# Daughterboard_Headers.net
KiCad netlist of a schematic drawn in Altium Designer
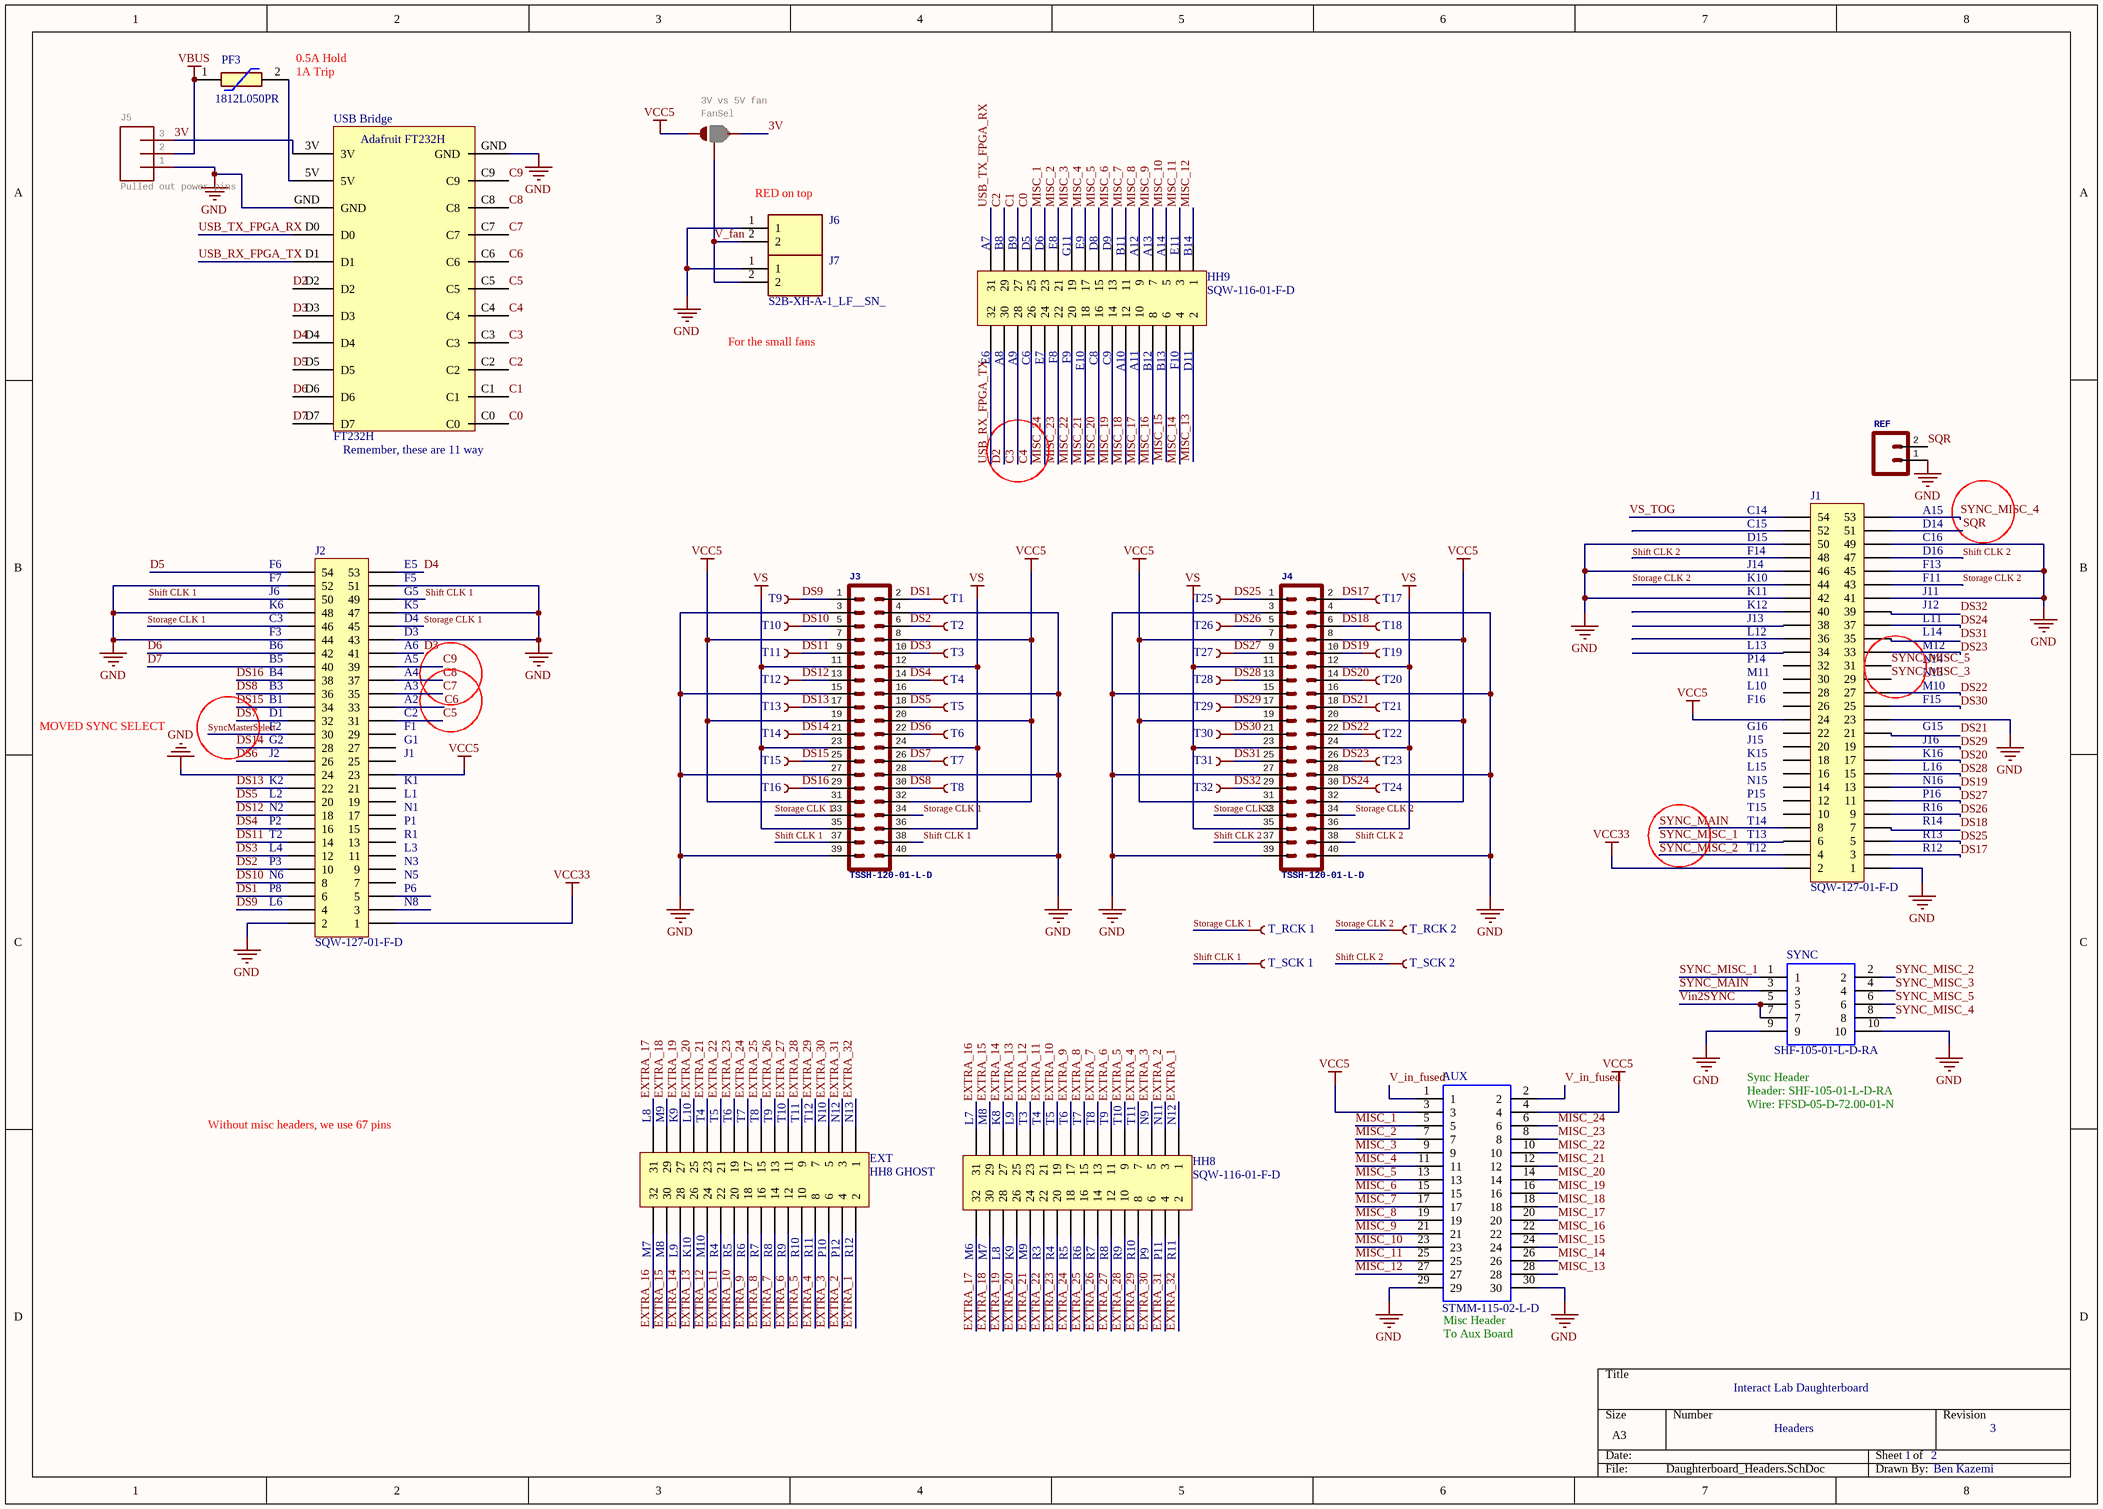
[diagram p0: Daughterboard_Headers.SchDoc]

(export (version "E")
  (design (tool "Eeschema 10.0.6"))
  (components
    (comp (ref "AUX")
      (value "STMM-115-02-L-D")
      (footprint "STMM-115-02-L-D")
      (fields (field (name "RS PART NUMBER") "9012513") (field (name "MOUSER PART NUMBER") "200-STMM11502LD"))
      (libsource (lib "InteractLab") (part "STMM-115-02-L-D"))
    )
    (comp (ref "EXT")
      (value "HH8 GHOST")
      (footprint "HDR2X16")
      (description "Header, 16-Pin, Dual row")
      (fields (field (name "PUBLISHER") "Altium Limited"))
      (libsource (lib "Miscellaneous Connectors") (part "Header 16X2"))
    )
    (comp (ref "FanSel")
      (value "3V vs 5V fan")
      (footprint "SMT-JUMPER_3_1-NC_PASTE_SILK")
      (libsource (lib "SparkFun-Jumpers.Library") (part "JUMPER-SMT_3_1-NC_PASTE_SILK"))
    )
    (comp (ref "HH8")
      (value "SQW-116-01-F-D")
      (footprint "Header 16X2 - 2mm")
      (description "Header, 16-Pin, Dual row")
      (fields (field (name "PUBLISHER") "Altium Limited"))
      (libsource (lib "InteractLab") (part "Header 16X2"))
    )
    (comp (ref "HH9")
      (value "SQW-116-01-F-D")
      (footprint "Header 16X2 - 2mm")
      (description "Header, 16-Pin, Dual row")
      (fields (field (name "PUBLISHER") "Altium Limited"))
      (libsource (lib "InteractLab") (part "Header 16X2"))
    )
    (comp (ref "J1")
      (value "SQW-127-01-F-D")
      (footprint "Header 27X2 - 2mm")
      (description "Header, 30-Pin, Dual row")
      (libsource (lib "InteractLab") (part "Header 27x2"))
    )
    (comp (ref "J2")
      (value "SQW-127-01-F-D")
      (footprint "Header 27X2 - 2mm")
      (description "Header, 30-Pin, Dual row")
      (libsource (lib "InteractLab") (part "Header 27x2"))
    )
    (comp (ref "J3")
      (value "TSSH-120-01-L-D")
      (footprint "2X20_Socket")
      (libsource (lib "InteractLab") (part "CONN_20X2"))
    )
    (comp (ref "J4")
      (value "TSSH-120-01-L-D")
      (footprint "2X20_Socket")
      (libsource (lib "InteractLab") (part "CONN_20X2"))
    )
    (comp (ref "J5")
      (value "Pulled out power pins")
      (footprint "1X03")
      (libsource (lib "SparkFun-Connectors.Library") (part "CONN_03"))
    )
    (comp (ref "J6")
      (value "S2B-XH-A-1_LF__SN_")
      (footprint "SamacSys:S2BXHA1LFSN")
      (description "Connector")
      (fields (field (name "MANUFACTURER_PART_NUMBER") "S2B-XH-A-1(LF)(SN)"))
      (libsource (lib "*") (part "S2B-XH-A-1_LF__SN_"))
    )
    (comp (ref "J7")
      (value "S2B-XH-A-1_LF__SN_")
      (footprint "SamacSys:S2BXHA1LFSN")
      (description "Connector")
      (fields (field (name "MANUFACTURER_PART_NUMBER") "S2B-XH-A-1(LF)(SN)"))
      (libsource (lib "*") (part "S2B-XH-A-1_LF__SN_"))
    )
    (comp (ref "PF3")
      (value "1812L050PR")
      (footprint "SamacSys:1812L010DR")
      (description "Resettable Fuse")
      (fields (field (name "MOUSER PART NUMBER") "576-1812L050PR"))
      (libsource (lib "*") (part "1812L050PR"))
    )
    (comp (ref "REF")
      (value "~")
      (footprint "1X02_LOCK_")
      (libsource (lib "SparkFun-Connectors") (part "CONN_02LOCK"))
    )
    (comp (ref "SYNC")
      (value "SHF-105-01-L-D-RA")
      (footprint "SHF-105-01-L-D-RA")
      (fields (field (name "RS PART NUMBER") "9011850"))
      (libsource (lib "InteractLab") (part "1.27mm Header 2x05 SHF-105-01-L-D-RA"))
    )
    (comp (ref "T1")
      (value "TEST-POINT3X5")
      (footprint "PAD.03X.05")
      (libsource (lib "SparkFun-Connectors") (part "TEST-POINT3X5"))
    )
    (comp (ref "T2")
      (value "TEST-POINT3X5")
      (footprint "PAD.03X.05")
      (libsource (lib "SparkFun-Connectors") (part "TEST-POINT3X5"))
    )
    (comp (ref "T3")
      (value "TEST-POINT3X5")
      (footprint "PAD.03X.05")
      (libsource (lib "SparkFun-Connectors") (part "TEST-POINT3X5"))
    )
    (comp (ref "T4")
      (value "TEST-POINT3X5")
      (footprint "PAD.03X.05")
      (libsource (lib "SparkFun-Connectors") (part "TEST-POINT3X5"))
    )
    (comp (ref "T5")
      (value "TEST-POINT3X5")
      (footprint "PAD.03X.05")
      (libsource (lib "SparkFun-Connectors") (part "TEST-POINT3X5"))
    )
    (comp (ref "T6")
      (value "TEST-POINT3X5")
      (footprint "PAD.03X.05")
      (libsource (lib "SparkFun-Connectors") (part "TEST-POINT3X5"))
    )
    (comp (ref "T7")
      (value "TEST-POINT3X5")
      (footprint "PAD.03X.05")
      (libsource (lib "SparkFun-Connectors") (part "TEST-POINT3X5"))
    )
    (comp (ref "T8")
      (value "TEST-POINT3X5")
      (footprint "PAD.03X.05")
      (libsource (lib "SparkFun-Connectors") (part "TEST-POINT3X5"))
    )
    (comp (ref "T9")
      (value "TEST-POINT3X5")
      (footprint "PAD.03X.05")
      (libsource (lib "SparkFun-Connectors") (part "TEST-POINT3X5"))
    )
    (comp (ref "T10")
      (value "TEST-POINT3X5")
      (footprint "PAD.03X.05")
      (libsource (lib "SparkFun-Connectors") (part "TEST-POINT3X5"))
    )
    (comp (ref "T11")
      (value "TEST-POINT3X5")
      (footprint "PAD.03X.05")
      (libsource (lib "SparkFun-Connectors") (part "TEST-POINT3X5"))
    )
    (comp (ref "T12")
      (value "TEST-POINT3X5")
      (footprint "PAD.03X.05")
      (libsource (lib "SparkFun-Connectors") (part "TEST-POINT3X5"))
    )
    (comp (ref "T13")
      (value "TEST-POINT3X5")
      (footprint "PAD.03X.05")
      (libsource (lib "SparkFun-Connectors") (part "TEST-POINT3X5"))
    )
    (comp (ref "T14")
      (value "TEST-POINT3X5")
      (footprint "PAD.03X.05")
      (libsource (lib "SparkFun-Connectors") (part "TEST-POINT3X5"))
    )
    (comp (ref "T15")
      (value "TEST-POINT3X5")
      (footprint "PAD.03X.05")
      (libsource (lib "SparkFun-Connectors") (part "TEST-POINT3X5"))
    )
    (comp (ref "T16")
      (value "TEST-POINT3X5")
      (footprint "PAD.03X.05")
      (libsource (lib "SparkFun-Connectors") (part "TEST-POINT3X5"))
    )
    (comp (ref "T17")
      (value "TEST-POINT3X5")
      (footprint "PAD.03X.05")
      (libsource (lib "SparkFun-Connectors") (part "TEST-POINT3X5"))
    )
    (comp (ref "T18")
      (value "TEST-POINT3X5")
      (footprint "PAD.03X.05")
      (libsource (lib "SparkFun-Connectors") (part "TEST-POINT3X5"))
    )
    (comp (ref "T19")
      (value "TEST-POINT3X5")
      (footprint "PAD.03X.05")
      (libsource (lib "SparkFun-Connectors") (part "TEST-POINT3X5"))
    )
    (comp (ref "T20")
      (value "TEST-POINT3X5")
      (footprint "PAD.03X.05")
      (libsource (lib "SparkFun-Connectors") (part "TEST-POINT3X5"))
    )
    (comp (ref "T21")
      (value "TEST-POINT3X5")
      (footprint "PAD.03X.05")
      (libsource (lib "SparkFun-Connectors") (part "TEST-POINT3X5"))
    )
    (comp (ref "T22")
      (value "TEST-POINT3X5")
      (footprint "PAD.03X.05")
      (libsource (lib "SparkFun-Connectors") (part "TEST-POINT3X5"))
    )
    (comp (ref "T23")
      (value "TEST-POINT3X5")
      (footprint "PAD.03X.05")
      (libsource (lib "SparkFun-Connectors") (part "TEST-POINT3X5"))
    )
    (comp (ref "T24")
      (value "TEST-POINT3X5")
      (footprint "PAD.03X.05")
      (libsource (lib "SparkFun-Connectors") (part "TEST-POINT3X5"))
    )
    (comp (ref "T25")
      (value "TEST-POINT3X5")
      (footprint "PAD.03X.05")
      (libsource (lib "SparkFun-Connectors") (part "TEST-POINT3X5"))
    )
    (comp (ref "T26")
      (value "TEST-POINT3X5")
      (footprint "PAD.03X.05")
      (libsource (lib "SparkFun-Connectors") (part "TEST-POINT3X5"))
    )
    (comp (ref "T27")
      (value "TEST-POINT3X5")
      (footprint "PAD.03X.05")
      (libsource (lib "SparkFun-Connectors") (part "TEST-POINT3X5"))
    )
    (comp (ref "T28")
      (value "TEST-POINT3X5")
      (footprint "PAD.03X.05")
      (libsource (lib "SparkFun-Connectors") (part "TEST-POINT3X5"))
    )
    (comp (ref "T29")
      (value "TEST-POINT3X5")
      (footprint "PAD.03X.05")
      (libsource (lib "SparkFun-Connectors") (part "TEST-POINT3X5"))
    )
    (comp (ref "T30")
      (value "TEST-POINT3X5")
      (footprint "PAD.03X.05")
      (libsource (lib "SparkFun-Connectors") (part "TEST-POINT3X5"))
    )
    (comp (ref "T31")
      (value "TEST-POINT3X5")
      (footprint "PAD.03X.05")
      (libsource (lib "SparkFun-Connectors") (part "TEST-POINT3X5"))
    )
    (comp (ref "T32")
      (value "TEST-POINT3X5")
      (footprint "PAD.03X.05")
      (libsource (lib "SparkFun-Connectors") (part "TEST-POINT3X5"))
    )
    (comp (ref "T_RCK 1")
      (value "TEST-POINT3X5")
      (footprint "PAD.03X.05")
      (libsource (lib "SparkFun-Connectors") (part "TEST-POINT3X5"))
    )
    (comp (ref "T_RCK 2")
      (value "TEST-POINT3X5")
      (footprint "PAD.03X.05")
      (libsource (lib "SparkFun-Connectors") (part "TEST-POINT3X5"))
    )
    (comp (ref "T_SCK 1")
      (value "TEST-POINT3X5")
      (footprint "PAD.03X.05")
      (libsource (lib "SparkFun-Connectors") (part "TEST-POINT3X5"))
    )
    (comp (ref "T_SCK 2")
      (value "TEST-POINT3X5")
      (footprint "PAD.03X.05")
      (libsource (lib "SparkFun-Connectors") (part "TEST-POINT3X5"))
    )
    (comp (ref "USB Bridge")
      (value "FT232H")
      (footprint "FT232H")
      (libsource (lib "InteractLab") (part "FT232H"))
    )
  )
  (nets
    (net (code "1") (name "/3V") (class "Default")
      (node (ref "FanSel") (pin "3") (pinfunction "3_3") (pintype "passive"))
      (node (ref "J5") (pin "3") (pinfunction "3_3") (pintype "passive"))
      (node (ref "USB Bridge") (pin "3V") (pinfunction "3V_3V") (pintype "passive"))
    )
    (net (code "2") (name "/C0") (class "Default")
      (node (ref "HH9") (pin "25") (pinfunction "25_25") (pintype "passive"))
      (node (ref "USB Bridge") (pin "C0") (pinfunction "C0_C0") (pintype "passive"))
    )
    (net (code "3") (name "/C1") (class "Default")
      (node (ref "HH9") (pin "27") (pinfunction "27_27") (pintype "passive"))
      (node (ref "USB Bridge") (pin "C1") (pinfunction "C1_C1") (pintype "passive"))
    )
    (net (code "4") (name "/C2") (class "Default")
      (node (ref "HH9") (pin "29") (pinfunction "29_29") (pintype "passive"))
      (node (ref "USB Bridge") (pin "C2") (pinfunction "C2_C2") (pintype "passive"))
    )
    (net (code "5") (name "/C3") (class "Default")
      (node (ref "HH9") (pin "28") (pinfunction "28_28") (pintype "passive"))
      (node (ref "USB Bridge") (pin "C3") (pinfunction "C3_C3") (pintype "passive"))
    )
    (net (code "6") (name "/C4") (class "Default")
      (node (ref "HH9") (pin "26") (pinfunction "26_26") (pintype "passive"))
      (node (ref "USB Bridge") (pin "C4") (pinfunction "C4_C4") (pintype "passive"))
    )
    (net (code "7") (name "/C5") (class "Default")
      (node (ref "J2") (pin "31") (pinfunction "31_31") (pintype "passive"))
      (node (ref "USB Bridge") (pin "C5") (pinfunction "C5_C5") (pintype "passive"))
    )
    (net (code "8") (name "/C6") (class "Default")
      (node (ref "J2") (pin "33") (pinfunction "33_33") (pintype "passive"))
      (node (ref "USB Bridge") (pin "C6") (pinfunction "C6_C6") (pintype "passive"))
    )
    (net (code "9") (name "/C7") (class "Default")
      (node (ref "J2") (pin "35") (pinfunction "35_35") (pintype "passive"))
      (node (ref "USB Bridge") (pin "C7") (pinfunction "C7_C7") (pintype "passive"))
    )
    (net (code "10") (name "/C8") (class "Default")
      (node (ref "J2") (pin "37") (pinfunction "37_37") (pintype "passive"))
      (node (ref "USB Bridge") (pin "C8") (pinfunction "C8_C8") (pintype "passive"))
    )
    (net (code "11") (name "/C9") (class "Default")
      (node (ref "J2") (pin "39") (pinfunction "39_39") (pintype "passive"))
      (node (ref "USB Bridge") (pin "C9") (pinfunction "C9_C9") (pintype "passive"))
    )
    (net (code "12") (name "/D2") (class "Default")
      (node (ref "HH9") (pin "30") (pinfunction "30_30") (pintype "passive"))
      (node (ref "USB Bridge") (pin "D2") (pinfunction "D2_D2") (pintype "passive"))
    )
    (net (code "13") (name "/D3") (class "Default")
      (node (ref "J2") (pin "41") (pinfunction "41_41") (pintype "passive"))
      (node (ref "USB Bridge") (pin "D3") (pinfunction "D3_D3") (pintype "passive"))
    )
    (net (code "14") (name "/D4") (class "Default")
      (node (ref "J2") (pin "53") (pinfunction "53_53") (pintype "passive"))
      (node (ref "USB Bridge") (pin "D4") (pinfunction "D4_D4") (pintype "passive"))
    )
    (net (code "15") (name "/D5") (class "Default")
      (node (ref "J2") (pin "54") (pinfunction "54_54") (pintype "passive"))
      (node (ref "USB Bridge") (pin "D5") (pinfunction "D5_D5") (pintype "passive"))
    )
    (net (code "16") (name "/D6") (class "Default")
      (node (ref "J2") (pin "42") (pinfunction "42_42") (pintype "passive"))
      (node (ref "USB Bridge") (pin "D6") (pinfunction "D6_D6") (pintype "passive"))
    )
    (net (code "17") (name "/D7") (class "Default")
      (node (ref "J2") (pin "40") (pinfunction "40_40") (pintype "passive"))
      (node (ref "USB Bridge") (pin "D7") (pinfunction "D7_D7") (pintype "passive"))
    )
    (net (code "18") (name "/DS1") (class "Default")
      (node (ref "J2") (pin "6") (pinfunction "6_6") (pintype "passive"))
      (node (ref "J3") (pin "2") (pinfunction "2_2") (pintype "passive"))
      (node (ref "T1") (pin "P$1") (pinfunction "1_P$1") (pintype "passive"))
    )
    (net (code "19") (name "/DS2") (class "Default")
      (node (ref "J2") (pin "10") (pinfunction "10_10") (pintype "passive"))
      (node (ref "J3") (pin "6") (pinfunction "6_6") (pintype "passive"))
      (node (ref "T2") (pin "P$1") (pinfunction "1_P$1") (pintype "passive"))
    )
    (net (code "20") (name "/DS3") (class "Default")
      (node (ref "J2") (pin "12") (pinfunction "12_12") (pintype "passive"))
      (node (ref "J3") (pin "10") (pinfunction "10_10") (pintype "passive"))
      (node (ref "T3") (pin "P$1") (pinfunction "1_P$1") (pintype "passive"))
    )
    (net (code "21") (name "/DS4") (class "Default")
      (node (ref "J2") (pin "16") (pinfunction "16_16") (pintype "passive"))
      (node (ref "J3") (pin "14") (pinfunction "14_14") (pintype "passive"))
      (node (ref "T4") (pin "P$1") (pinfunction "1_P$1") (pintype "passive"))
    )
    (net (code "22") (name "/DS5") (class "Default")
      (node (ref "J2") (pin "20") (pinfunction "20_20") (pintype "passive"))
      (node (ref "J3") (pin "18") (pinfunction "18_18") (pintype "passive"))
      (node (ref "T5") (pin "P$1") (pinfunction "1_P$1") (pintype "passive"))
    )
    (net (code "23") (name "/DS6") (class "Default")
      (node (ref "J2") (pin "26") (pinfunction "26_26") (pintype "passive"))
      (node (ref "J3") (pin "22") (pinfunction "22_22") (pintype "passive"))
      (node (ref "T6") (pin "P$1") (pinfunction "1_P$1") (pintype "passive"))
    )
    (net (code "24") (name "/DS7") (class "Default")
      (node (ref "J2") (pin "32") (pinfunction "32_32") (pintype "passive"))
      (node (ref "J3") (pin "26") (pinfunction "26_26") (pintype "passive"))
      (node (ref "T7") (pin "P$1") (pinfunction "1_P$1") (pintype "passive"))
    )
    (net (code "25") (name "/DS8") (class "Default")
      (node (ref "J2") (pin "36") (pinfunction "36_36") (pintype "passive"))
      (node (ref "J3") (pin "30") (pinfunction "30_30") (pintype "passive"))
      (node (ref "T8") (pin "P$1") (pinfunction "1_P$1") (pintype "passive"))
    )
    (net (code "26") (name "/DS9") (class "Default")
      (node (ref "J2") (pin "4") (pinfunction "4_4") (pintype "passive"))
      (node (ref "J3") (pin "1") (pinfunction "1_1") (pintype "passive"))
      (node (ref "T9") (pin "P$1") (pinfunction "1_P$1") (pintype "passive"))
    )
    (net (code "27") (name "/DS10") (class "Default")
      (node (ref "J2") (pin "8") (pinfunction "8_8") (pintype "passive"))
      (node (ref "J3") (pin "5") (pinfunction "5_5") (pintype "passive"))
      (node (ref "T10") (pin "P$1") (pinfunction "1_P$1") (pintype "passive"))
    )
    (net (code "28") (name "/DS11") (class "Default")
      (node (ref "J2") (pin "14") (pinfunction "14_14") (pintype "passive"))
      (node (ref "J3") (pin "9") (pinfunction "9_9") (pintype "passive"))
      (node (ref "T11") (pin "P$1") (pinfunction "1_P$1") (pintype "passive"))
    )
    (net (code "29") (name "/DS12") (class "Default")
      (node (ref "J2") (pin "18") (pinfunction "18_18") (pintype "passive"))
      (node (ref "J3") (pin "13") (pinfunction "13_13") (pintype "passive"))
      (node (ref "T12") (pin "P$1") (pinfunction "1_P$1") (pintype "passive"))
    )
    (net (code "30") (name "/DS13") (class "Default")
      (node (ref "J2") (pin "22") (pinfunction "22_22") (pintype "passive"))
      (node (ref "J3") (pin "17") (pinfunction "17_17") (pintype "passive"))
      (node (ref "T13") (pin "P$1") (pinfunction "1_P$1") (pintype "passive"))
    )
    (net (code "31") (name "/DS14") (class "Default")
      (node (ref "J2") (pin "28") (pinfunction "28_28") (pintype "passive"))
      (node (ref "J3") (pin "21") (pinfunction "21_21") (pintype "passive"))
      (node (ref "T14") (pin "P$1") (pinfunction "1_P$1") (pintype "passive"))
    )
    (net (code "32") (name "/DS15") (class "Default")
      (node (ref "J2") (pin "34") (pinfunction "34_34") (pintype "passive"))
      (node (ref "J3") (pin "25") (pinfunction "25_25") (pintype "passive"))
      (node (ref "T15") (pin "P$1") (pinfunction "1_P$1") (pintype "passive"))
    )
    (net (code "33") (name "/DS16") (class "Default")
      (node (ref "J2") (pin "38") (pinfunction "38_38") (pintype "passive"))
      (node (ref "J3") (pin "29") (pinfunction "29_29") (pintype "passive"))
      (node (ref "T16") (pin "P$1") (pinfunction "1_P$1") (pintype "passive"))
    )
    (net (code "34") (name "/DS17") (class "Default")
      (node (ref "J1") (pin "3") (pinfunction "3_3") (pintype "passive"))
      (node (ref "J4") (pin "2") (pinfunction "2_2") (pintype "passive"))
      (node (ref "T17") (pin "P$1") (pinfunction "1_P$1") (pintype "passive"))
    )
    (net (code "35") (name "/DS18") (class "Default")
      (node (ref "J1") (pin "7") (pinfunction "7_7") (pintype "passive"))
      (node (ref "J4") (pin "6") (pinfunction "6_6") (pintype "passive"))
      (node (ref "T18") (pin "P$1") (pinfunction "1_P$1") (pintype "passive"))
    )
    (net (code "36") (name "/DS19") (class "Default")
      (node (ref "J1") (pin "13") (pinfunction "13_13") (pintype "passive"))
      (node (ref "J4") (pin "10") (pinfunction "10_10") (pintype "passive"))
      (node (ref "T19") (pin "P$1") (pinfunction "1_P$1") (pintype "passive"))
    )
    (net (code "37") (name "/DS20") (class "Default")
      (node (ref "J1") (pin "17") (pinfunction "17_17") (pintype "passive"))
      (node (ref "J4") (pin "14") (pinfunction "14_14") (pintype "passive"))
      (node (ref "T20") (pin "P$1") (pinfunction "1_P$1") (pintype "passive"))
    )
    (net (code "38") (name "/DS21") (class "Default")
      (node (ref "J1") (pin "21") (pinfunction "21_21") (pintype "passive"))
      (node (ref "J4") (pin "18") (pinfunction "18_18") (pintype "passive"))
      (node (ref "T21") (pin "P$1") (pinfunction "1_P$1") (pintype "passive"))
    )
    (net (code "39") (name "/DS22") (class "Default")
      (node (ref "J1") (pin "27") (pinfunction "27_27") (pintype "passive"))
      (node (ref "J4") (pin "22") (pinfunction "22_22") (pintype "passive"))
      (node (ref "T22") (pin "P$1") (pinfunction "1_P$1") (pintype "passive"))
    )
    (net (code "40") (name "/DS23") (class "Default")
      (node (ref "J1") (pin "33") (pinfunction "33_33") (pintype "passive"))
      (node (ref "J4") (pin "26") (pinfunction "26_26") (pintype "passive"))
      (node (ref "T23") (pin "P$1") (pinfunction "1_P$1") (pintype "passive"))
    )
    (net (code "41") (name "/DS24") (class "Default")
      (node (ref "J1") (pin "37") (pinfunction "37_37") (pintype "passive"))
      (node (ref "J4") (pin "30") (pinfunction "30_30") (pintype "passive"))
      (node (ref "T24") (pin "P$1") (pinfunction "1_P$1") (pintype "passive"))
    )
    (net (code "42") (name "/DS25") (class "Default")
      (node (ref "J1") (pin "5") (pinfunction "5_5") (pintype "passive"))
      (node (ref "J4") (pin "1") (pinfunction "1_1") (pintype "passive"))
      (node (ref "T25") (pin "P$1") (pinfunction "1_P$1") (pintype "passive"))
    )
    (net (code "43") (name "/DS26") (class "Default")
      (node (ref "J1") (pin "9") (pinfunction "9_9") (pintype "passive"))
      (node (ref "J4") (pin "5") (pinfunction "5_5") (pintype "passive"))
      (node (ref "T26") (pin "P$1") (pinfunction "1_P$1") (pintype "passive"))
    )
    (net (code "44") (name "/DS27") (class "Default")
      (node (ref "J1") (pin "11") (pinfunction "11_11") (pintype "passive"))
      (node (ref "J4") (pin "9") (pinfunction "9_9") (pintype "passive"))
      (node (ref "T27") (pin "P$1") (pinfunction "1_P$1") (pintype "passive"))
    )
    (net (code "45") (name "/DS28") (class "Default")
      (node (ref "J1") (pin "15") (pinfunction "15_15") (pintype "passive"))
      (node (ref "J4") (pin "13") (pinfunction "13_13") (pintype "passive"))
      (node (ref "T28") (pin "P$1") (pinfunction "1_P$1") (pintype "passive"))
    )
    (net (code "46") (name "/DS29") (class "Default")
      (node (ref "J1") (pin "19") (pinfunction "19_19") (pintype "passive"))
      (node (ref "J4") (pin "17") (pinfunction "17_17") (pintype "passive"))
      (node (ref "T29") (pin "P$1") (pinfunction "1_P$1") (pintype "passive"))
    )
    (net (code "47") (name "/DS30") (class "Default")
      (node (ref "J1") (pin "25") (pinfunction "25_25") (pintype "passive"))
      (node (ref "J4") (pin "21") (pinfunction "21_21") (pintype "passive"))
      (node (ref "T30") (pin "P$1") (pinfunction "1_P$1") (pintype "passive"))
    )
    (net (code "48") (name "/DS31") (class "Default")
      (node (ref "J1") (pin "35") (pinfunction "35_35") (pintype "passive"))
      (node (ref "J4") (pin "25") (pinfunction "25_25") (pintype "passive"))
      (node (ref "T31") (pin "P$1") (pinfunction "1_P$1") (pintype "passive"))
    )
    (net (code "49") (name "/DS32") (class "Default")
      (node (ref "J1") (pin "39") (pinfunction "39_39") (pintype "passive"))
      (node (ref "J4") (pin "29") (pinfunction "29_29") (pintype "passive"))
      (node (ref "T32") (pin "P$1") (pinfunction "1_P$1") (pintype "passive"))
    )
    (net (code "50") (name "/EXTRA_1") (class "Default")
      (node (ref "EXT") (pin "2") (pinfunction "2_2") (pintype "passive"))
      (node (ref "HH8") (pin "1") (pinfunction "1_1") (pintype "passive"))
    )
    (net (code "51") (name "/EXTRA_2") (class "Default")
      (node (ref "EXT") (pin "4") (pinfunction "4_4") (pintype "passive"))
      (node (ref "HH8") (pin "3") (pinfunction "3_3") (pintype "passive"))
    )
    (net (code "52") (name "/EXTRA_3") (class "Default")
      (node (ref "EXT") (pin "6") (pinfunction "6_6") (pintype "passive"))
      (node (ref "HH8") (pin "5") (pinfunction "5_5") (pintype "passive"))
    )
    (net (code "53") (name "/EXTRA_4") (class "Default")
      (node (ref "EXT") (pin "8") (pinfunction "8_8") (pintype "passive"))
      (node (ref "HH8") (pin "7") (pinfunction "7_7") (pintype "passive"))
    )
    (net (code "54") (name "/EXTRA_5") (class "Default")
      (node (ref "EXT") (pin "10") (pinfunction "10_10") (pintype "passive"))
      (node (ref "HH8") (pin "9") (pinfunction "9_9") (pintype "passive"))
    )
    (net (code "55") (name "/EXTRA_6") (class "Default")
      (node (ref "EXT") (pin "12") (pinfunction "12_12") (pintype "passive"))
      (node (ref "HH8") (pin "11") (pinfunction "11_11") (pintype "passive"))
    )
    (net (code "56") (name "/EXTRA_7") (class "Default")
      (node (ref "EXT") (pin "14") (pinfunction "14_14") (pintype "passive"))
      (node (ref "HH8") (pin "13") (pinfunction "13_13") (pintype "passive"))
    )
    (net (code "57") (name "/EXTRA_8") (class "Default")
      (node (ref "EXT") (pin "16") (pinfunction "16_16") (pintype "passive"))
      (node (ref "HH8") (pin "15") (pinfunction "15_15") (pintype "passive"))
    )
    (net (code "58") (name "/EXTRA_9") (class "Default")
      (node (ref "EXT") (pin "18") (pinfunction "18_18") (pintype "passive"))
      (node (ref "HH8") (pin "17") (pinfunction "17_17") (pintype "passive"))
    )
    (net (code "59") (name "/EXTRA_10") (class "Default")
      (node (ref "EXT") (pin "20") (pinfunction "20_20") (pintype "passive"))
      (node (ref "HH8") (pin "19") (pinfunction "19_19") (pintype "passive"))
    )
    (net (code "60") (name "/EXTRA_11") (class "Default")
      (node (ref "EXT") (pin "22") (pinfunction "22_22") (pintype "passive"))
      (node (ref "HH8") (pin "21") (pinfunction "21_21") (pintype "passive"))
    )
    (net (code "61") (name "/EXTRA_12") (class "Default")
      (node (ref "EXT") (pin "24") (pinfunction "24_24") (pintype "passive"))
      (node (ref "HH8") (pin "23") (pinfunction "23_23") (pintype "passive"))
    )
    (net (code "62") (name "/EXTRA_13") (class "Default")
      (node (ref "EXT") (pin "26") (pinfunction "26_26") (pintype "passive"))
      (node (ref "HH8") (pin "25") (pinfunction "25_25") (pintype "passive"))
    )
    (net (code "63") (name "/EXTRA_14") (class "Default")
      (node (ref "EXT") (pin "28") (pinfunction "28_28") (pintype "passive"))
      (node (ref "HH8") (pin "27") (pinfunction "27_27") (pintype "passive"))
    )
    (net (code "64") (name "/EXTRA_15") (class "Default")
      (node (ref "EXT") (pin "30") (pinfunction "30_30") (pintype "passive"))
      (node (ref "HH8") (pin "29") (pinfunction "29_29") (pintype "passive"))
    )
    (net (code "65") (name "/EXTRA_16") (class "Default")
      (node (ref "EXT") (pin "32") (pinfunction "32_32") (pintype "passive"))
      (node (ref "HH8") (pin "31") (pinfunction "31_31") (pintype "passive"))
    )
    (net (code "66") (name "/EXTRA_17") (class "Default")
      (node (ref "EXT") (pin "31") (pinfunction "31_31") (pintype "passive"))
      (node (ref "HH8") (pin "32") (pinfunction "32_32") (pintype "passive"))
    )
    (net (code "67") (name "/EXTRA_18") (class "Default")
      (node (ref "EXT") (pin "29") (pinfunction "29_29") (pintype "passive"))
      (node (ref "HH8") (pin "30") (pinfunction "30_30") (pintype "passive"))
    )
    (net (code "68") (name "/EXTRA_19") (class "Default")
      (node (ref "EXT") (pin "27") (pinfunction "27_27") (pintype "passive"))
      (node (ref "HH8") (pin "28") (pinfunction "28_28") (pintype "passive"))
    )
    (net (code "69") (name "/EXTRA_20") (class "Default")
      (node (ref "EXT") (pin "25") (pinfunction "25_25") (pintype "passive"))
      (node (ref "HH8") (pin "26") (pinfunction "26_26") (pintype "passive"))
    )
    (net (code "70") (name "/EXTRA_21") (class "Default")
      (node (ref "EXT") (pin "23") (pinfunction "23_23") (pintype "passive"))
      (node (ref "HH8") (pin "24") (pinfunction "24_24") (pintype "passive"))
    )
    (net (code "71") (name "/EXTRA_22") (class "Default")
      (node (ref "EXT") (pin "21") (pinfunction "21_21") (pintype "passive"))
      (node (ref "HH8") (pin "22") (pinfunction "22_22") (pintype "passive"))
    )
    (net (code "72") (name "/EXTRA_23") (class "Default")
      (node (ref "EXT") (pin "19") (pinfunction "19_19") (pintype "passive"))
      (node (ref "HH8") (pin "20") (pinfunction "20_20") (pintype "passive"))
    )
    (net (code "73") (name "/EXTRA_24") (class "Default")
      (node (ref "EXT") (pin "17") (pinfunction "17_17") (pintype "passive"))
      (node (ref "HH8") (pin "18") (pinfunction "18_18") (pintype "passive"))
    )
    (net (code "74") (name "/EXTRA_25") (class "Default")
      (node (ref "EXT") (pin "15") (pinfunction "15_15") (pintype "passive"))
      (node (ref "HH8") (pin "16") (pinfunction "16_16") (pintype "passive"))
    )
    (net (code "75") (name "/EXTRA_26") (class "Default")
      (node (ref "EXT") (pin "13") (pinfunction "13_13") (pintype "passive"))
      (node (ref "HH8") (pin "14") (pinfunction "14_14") (pintype "passive"))
    )
    (net (code "76") (name "/EXTRA_27") (class "Default")
      (node (ref "EXT") (pin "11") (pinfunction "11_11") (pintype "passive"))
      (node (ref "HH8") (pin "12") (pinfunction "12_12") (pintype "passive"))
    )
    (net (code "77") (name "/EXTRA_28") (class "Default")
      (node (ref "EXT") (pin "9") (pinfunction "9_9") (pintype "passive"))
      (node (ref "HH8") (pin "10") (pinfunction "10_10") (pintype "passive"))
    )
    (net (code "78") (name "/EXTRA_29") (class "Default")
      (node (ref "EXT") (pin "7") (pinfunction "7_7") (pintype "passive"))
      (node (ref "HH8") (pin "8") (pinfunction "8_8") (pintype "passive"))
    )
    (net (code "79") (name "/EXTRA_30") (class "Default")
      (node (ref "EXT") (pin "5") (pinfunction "5_5") (pintype "passive"))
      (node (ref "HH8") (pin "6") (pinfunction "6_6") (pintype "passive"))
    )
    (net (code "80") (name "/EXTRA_31") (class "Default")
      (node (ref "EXT") (pin "3") (pinfunction "3_3") (pintype "passive"))
      (node (ref "HH8") (pin "4") (pinfunction "4_4") (pintype "passive"))
    )
    (net (code "81") (name "/EXTRA_32") (class "Default")
      (node (ref "EXT") (pin "1") (pinfunction "1_1") (pintype "passive"))
      (node (ref "HH8") (pin "2") (pinfunction "2_2") (pintype "passive"))
    )
    (net (code "82") (name "/MISC_1") (class "Default")
      (node (ref "AUX") (pin "5") (pinfunction "5_5") (pintype "passive"))
      (node (ref "HH9") (pin "23") (pinfunction "23_23") (pintype "passive"))
    )
    (net (code "83") (name "/MISC_2") (class "Default")
      (node (ref "AUX") (pin "7") (pinfunction "7_7") (pintype "passive"))
      (node (ref "HH9") (pin "21") (pinfunction "21_21") (pintype "passive"))
    )
    (net (code "84") (name "/MISC_3") (class "Default")
      (node (ref "AUX") (pin "9") (pinfunction "9_9") (pintype "passive"))
      (node (ref "HH9") (pin "19") (pinfunction "19_19") (pintype "passive"))
    )
    (net (code "85") (name "/MISC_4") (class "Default")
      (node (ref "AUX") (pin "11") (pinfunction "11_11") (pintype "passive"))
      (node (ref "HH9") (pin "17") (pinfunction "17_17") (pintype "passive"))
    )
    (net (code "86") (name "/MISC_5") (class "Default")
      (node (ref "AUX") (pin "13") (pinfunction "13_13") (pintype "passive"))
      (node (ref "HH9") (pin "15") (pinfunction "15_15") (pintype "passive"))
    )
    (net (code "87") (name "/MISC_6") (class "Default")
      (node (ref "AUX") (pin "15") (pinfunction "15_15") (pintype "passive"))
      (node (ref "HH9") (pin "13") (pinfunction "13_13") (pintype "passive"))
    )
    (net (code "88") (name "/MISC_7") (class "Default")
      (node (ref "AUX") (pin "17") (pinfunction "17_17") (pintype "passive"))
      (node (ref "HH9") (pin "11") (pinfunction "11_11") (pintype "passive"))
    )
    (net (code "89") (name "/MISC_8") (class "Default")
      (node (ref "AUX") (pin "19") (pinfunction "19_19") (pintype "passive"))
      (node (ref "HH9") (pin "9") (pinfunction "9_9") (pintype "passive"))
    )
    (net (code "90") (name "/MISC_9") (class "Default")
      (node (ref "AUX") (pin "21") (pinfunction "21_21") (pintype "passive"))
      (node (ref "HH9") (pin "7") (pinfunction "7_7") (pintype "passive"))
    )
    (net (code "91") (name "/MISC_10") (class "Default")
      (node (ref "AUX") (pin "23") (pinfunction "23_23") (pintype "passive"))
      (node (ref "HH9") (pin "5") (pinfunction "5_5") (pintype "passive"))
    )
    (net (code "92") (name "/MISC_11") (class "Default")
      (node (ref "AUX") (pin "25") (pinfunction "25_25") (pintype "passive"))
      (node (ref "HH9") (pin "3") (pinfunction "3_3") (pintype "passive"))
    )
    (net (code "93") (name "/MISC_12") (class "Default")
      (node (ref "AUX") (pin "27") (pinfunction "27_27") (pintype "passive"))
      (node (ref "HH9") (pin "1") (pinfunction "1_1") (pintype "passive"))
    )
    (net (code "94") (name "/MISC_13") (class "Default")
      (node (ref "AUX") (pin "28") (pinfunction "28_28") (pintype "passive"))
      (node (ref "HH9") (pin "2") (pinfunction "2_2") (pintype "passive"))
    )
    (net (code "95") (name "/MISC_14") (class "Default")
      (node (ref "AUX") (pin "26") (pinfunction "26_26") (pintype "passive"))
      (node (ref "HH9") (pin "4") (pinfunction "4_4") (pintype "passive"))
    )
    (net (code "96") (name "/MISC_15") (class "Default")
      (node (ref "AUX") (pin "24") (pinfunction "24_24") (pintype "passive"))
      (node (ref "HH9") (pin "6") (pinfunction "6_6") (pintype "passive"))
    )
    (net (code "97") (name "/MISC_16") (class "Default")
      (node (ref "AUX") (pin "22") (pinfunction "22_22") (pintype "passive"))
      (node (ref "HH9") (pin "8") (pinfunction "8_8") (pintype "passive"))
    )
    (net (code "98") (name "/MISC_17") (class "Default")
      (node (ref "AUX") (pin "20") (pinfunction "20_20") (pintype "passive"))
      (node (ref "HH9") (pin "10") (pinfunction "10_10") (pintype "passive"))
    )
    (net (code "99") (name "/MISC_18") (class "Default")
      (node (ref "AUX") (pin "18") (pinfunction "18_18") (pintype "passive"))
      (node (ref "HH9") (pin "12") (pinfunction "12_12") (pintype "passive"))
    )
    (net (code "100") (name "/MISC_19") (class "Default")
      (node (ref "AUX") (pin "16") (pinfunction "16_16") (pintype "passive"))
      (node (ref "HH9") (pin "14") (pinfunction "14_14") (pintype "passive"))
    )
    (net (code "101") (name "/MISC_20") (class "Default")
      (node (ref "AUX") (pin "14") (pinfunction "14_14") (pintype "passive"))
      (node (ref "HH9") (pin "16") (pinfunction "16_16") (pintype "passive"))
    )
    (net (code "102") (name "/MISC_21") (class "Default")
      (node (ref "AUX") (pin "12") (pinfunction "12_12") (pintype "passive"))
      (node (ref "HH9") (pin "18") (pinfunction "18_18") (pintype "passive"))
    )
    (net (code "103") (name "/MISC_22") (class "Default")
      (node (ref "AUX") (pin "10") (pinfunction "10_10") (pintype "passive"))
      (node (ref "HH9") (pin "20") (pinfunction "20_20") (pintype "passive"))
    )
    (net (code "104") (name "/MISC_23") (class "Default")
      (node (ref "AUX") (pin "8") (pinfunction "8_8") (pintype "passive"))
      (node (ref "HH9") (pin "22") (pinfunction "22_22") (pintype "passive"))
    )
    (net (code "105") (name "/MISC_24") (class "Default")
      (node (ref "AUX") (pin "6") (pinfunction "6_6") (pintype "passive"))
      (node (ref "HH9") (pin "24") (pinfunction "24_24") (pintype "passive"))
    )
    (net (code "106") (name "/SQR") (class "Default")
      (node (ref "J1") (pin "51") (pinfunction "51_51") (pintype "passive"))
      (node (ref "REF") (pin "2") (pinfunction "2_2") (pintype "passive"))
    )
    (net (code "107") (name "/SYNC_MAIN") (class "Default")
      (node (ref "J1") (pin "8") (pinfunction "8_8") (pintype "passive"))
      (node (ref "SYNC") (pin "3") (pinfunction "3_3") (pintype "passive"))
    )
    (net (code "108") (name "/SYNC_MISC_1") (class "Default")
      (node (ref "J1") (pin "6") (pinfunction "6_6") (pintype "passive"))
      (node (ref "SYNC") (pin "1") (pinfunction "1_1") (pintype "passive"))
    )
    (net (code "109") (name "/SYNC_MISC_2") (class "Default")
      (node (ref "J1") (pin "4") (pinfunction "4_4") (pintype "passive"))
      (node (ref "SYNC") (pin "2") (pinfunction "2_2") (pintype "passive"))
    )
    (net (code "110") (name "/SYNC_MISC_3") (class "Default")
      (node (ref "J1") (pin "29") (pinfunction "29_29") (pintype "passive"))
      (node (ref "SYNC") (pin "4") (pinfunction "4_4") (pintype "passive"))
    )
    (net (code "111") (name "/SYNC_MISC_4") (class "Default")
      (node (ref "J1") (pin "53") (pinfunction "53_53") (pintype "passive"))
      (node (ref "SYNC") (pin "8") (pinfunction "8_8") (pintype "passive"))
    )
    (net (code "112") (name "/SYNC_MISC_5") (class "Default")
      (node (ref "J1") (pin "31") (pinfunction "31_31") (pintype "passive"))
      (node (ref "SYNC") (pin "6") (pinfunction "6_6") (pintype "passive"))
    )
    (net (code "113") (name "/Shift CLK 1") (class "Default")
      (node (ref "J2") (pin "49") (pinfunction "49_49") (pintype "passive"))
      (node (ref "J2") (pin "50") (pinfunction "50_50") (pintype "passive"))
      (node (ref "J3") (pin "37") (pinfunction "37_37") (pintype "passive"))
      (node (ref "J3") (pin "38") (pinfunction "38_38") (pintype "passive"))
      (node (ref "T_SCK 1") (pin "P$1") (pinfunction "1_P$1") (pintype "passive"))
    )
    (net (code "114") (name "/Shift CLK 2") (class "Default")
      (node (ref "J1") (pin "47") (pinfunction "47_47") (pintype "passive"))
      (node (ref "J1") (pin "48") (pinfunction "48_48") (pintype "passive"))
      (node (ref "J4") (pin "37") (pinfunction "37_37") (pintype "passive"))
      (node (ref "J4") (pin "38") (pinfunction "38_38") (pintype "passive"))
      (node (ref "T_SCK 2") (pin "P$1") (pinfunction "1_P$1") (pintype "passive"))
    )
    (net (code "115") (name "/Storage CLK 1") (class "Default")
      (node (ref "J2") (pin "45") (pinfunction "45_45") (pintype "passive"))
      (node (ref "J2") (pin "46") (pinfunction "46_46") (pintype "passive"))
      (node (ref "J3") (pin "33") (pinfunction "33_33") (pintype "passive"))
      (node (ref "J3") (pin "34") (pinfunction "34_34") (pintype "passive"))
      (node (ref "T_RCK 1") (pin "P$1") (pinfunction "1_P$1") (pintype "passive"))
    )
    (net (code "116") (name "/Storage CLK 2") (class "Default")
      (node (ref "J1") (pin "43") (pinfunction "43_43") (pintype "passive"))
      (node (ref "J1") (pin "44") (pinfunction "44_44") (pintype "passive"))
      (node (ref "J4") (pin "33") (pinfunction "33_33") (pintype "passive"))
      (node (ref "J4") (pin "34") (pinfunction "34_34") (pintype "passive"))
      (node (ref "T_RCK 2") (pin "P$1") (pinfunction "1_P$1") (pintype "passive"))
    )
    (net (code "117") (name "/SyncMasterSelect") (class "Default")
      (node (ref "J2") (pin "30") (pinfunction "30_30") (pintype "passive"))
    )
    (net (code "118") (name "/USB_RX_FPGA_TX") (class "Default")
      (node (ref "HH9") (pin "32") (pinfunction "32_32") (pintype "passive"))
      (node (ref "USB Bridge") (pin "D1") (pinfunction "D1_D1") (pintype "passive"))
    )
    (net (code "119") (name "/USB_TX_FPGA_RX") (class "Default")
      (node (ref "HH9") (pin "31") (pinfunction "31_31") (pintype "passive"))
      (node (ref "USB Bridge") (pin "D0") (pinfunction "D0_D0") (pintype "passive"))
    )
    (net (code "120") (name "/VS_TOG") (class "Default")
      (node (ref "J1") (pin "54") (pinfunction "54_54") (pintype "passive"))
    )
    (net (code "121") (name "/V_fan") (class "Default")
      (node (ref "FanSel") (pin "2") (pinfunction "2_2") (pintype "passive"))
      (node (ref "J6") (pin "2") (pinfunction "2_2") (pintype "passive"))
      (node (ref "J7") (pin "2") (pinfunction "2_2") (pintype "passive"))
    )
    (net (code "122") (name "/V_in_fused") (class "Default")
      (node (ref "AUX") (pin "1") (pinfunction "1_1") (pintype "passive"))
      (node (ref "AUX") (pin "2") (pinfunction "2_2") (pintype "passive"))
    )
    (net (code "123") (name "/Vin2SYNC") (class "Default")
      (node (ref "SYNC") (pin "5") (pinfunction "5_5") (pintype "passive"))
      (node (ref "SYNC") (pin "7") (pinfunction "7_7") (pintype "passive"))
    )
    (net (code "124") (name "GND") (class "Default")
      (node (ref "AUX") (pin "29") (pinfunction "29_29") (pintype "passive"))
      (node (ref "AUX") (pin "30") (pinfunction "30_30") (pintype "passive"))
      (node (ref "J1") (pin "1") (pinfunction "1_1") (pintype "passive"))
      (node (ref "J1") (pin "23") (pinfunction "23_23") (pintype "passive"))
      (node (ref "J1") (pin "41") (pinfunction "41_41") (pintype "passive"))
      (node (ref "J1") (pin "42") (pinfunction "42_42") (pintype "passive"))
      (node (ref "J1") (pin "45") (pinfunction "45_45") (pintype "passive"))
      (node (ref "J1") (pin "46") (pinfunction "46_46") (pintype "passive"))
      (node (ref "J1") (pin "49") (pinfunction "49_49") (pintype "passive"))
      (node (ref "J1") (pin "50") (pinfunction "50_50") (pintype "passive"))
      (node (ref "J2") (pin "2") (pinfunction "2_2") (pintype "passive"))
      (node (ref "J2") (pin "24") (pinfunction "24_24") (pintype "passive"))
      (node (ref "J2") (pin "43") (pinfunction "43_43") (pintype "passive"))
      (node (ref "J2") (pin "44") (pinfunction "44_44") (pintype "passive"))
      (node (ref "J2") (pin "47") (pinfunction "47_47") (pintype "passive"))
      (node (ref "J2") (pin "48") (pinfunction "48_48") (pintype "passive"))
      (node (ref "J2") (pin "51") (pinfunction "51_51") (pintype "passive"))
      (node (ref "J2") (pin "52") (pinfunction "52_52") (pintype "passive"))
      (node (ref "J3") (pin "15") (pinfunction "15_15") (pintype "passive"))
      (node (ref "J3") (pin "16") (pinfunction "16_16") (pintype "passive"))
      (node (ref "J3") (pin "27") (pinfunction "27_27") (pintype "passive"))
      (node (ref "J3") (pin "28") (pinfunction "28_28") (pintype "passive"))
      (node (ref "J3") (pin "3") (pinfunction "3_3") (pintype "passive"))
      (node (ref "J3") (pin "39") (pinfunction "39_39") (pintype "passive"))
      (node (ref "J3") (pin "4") (pinfunction "4_4") (pintype "passive"))
      (node (ref "J3") (pin "40") (pinfunction "40_40") (pintype "passive"))
      (node (ref "J4") (pin "15") (pinfunction "15_15") (pintype "passive"))
      (node (ref "J4") (pin "16") (pinfunction "16_16") (pintype "passive"))
      (node (ref "J4") (pin "27") (pinfunction "27_27") (pintype "passive"))
      (node (ref "J4") (pin "28") (pinfunction "28_28") (pintype "passive"))
      (node (ref "J4") (pin "3") (pinfunction "3_3") (pintype "passive"))
      (node (ref "J4") (pin "39") (pinfunction "39_39") (pintype "passive"))
      (node (ref "J4") (pin "4") (pinfunction "4_4") (pintype "passive"))
      (node (ref "J4") (pin "40") (pinfunction "40_40") (pintype "passive"))
      (node (ref "J5") (pin "1") (pinfunction "1_1") (pintype "passive"))
      (node (ref "J6") (pin "1") (pinfunction "1_1") (pintype "passive"))
      (node (ref "J7") (pin "1") (pinfunction "1_1") (pintype "passive"))
      (node (ref "REF") (pin "1") (pinfunction "1_1") (pintype "passive"))
      (node (ref "SYNC") (pin "10") (pinfunction "10_10") (pintype "passive"))
      (node (ref "SYNC") (pin "9") (pinfunction "9_9") (pintype "passive"))
      (node (ref "USB Bridge") (pin "GND") (pinfunction "GND_GND") (pintype "passive"))
    )
    (net (code "125") (name "Net-(PF3-Pad2)") (class "Default")
      (node (ref "PF3") (pin "2") (pinfunction "2_2") (pintype "passive"))
      (node (ref "USB Bridge") (pin "5V") (pinfunction "5V_5V") (pintype "passive"))
    )
    (net (code "126") (name "VBUS") (class "Default")
      (node (ref "J5") (pin "2") (pinfunction "2_2") (pintype "passive"))
      (node (ref "PF3") (pin "1") (pinfunction "1_1") (pintype "passive"))
    )
    (net (code "127") (name "VCC5") (class "Default")
      (node (ref "AUX") (pin "3") (pinfunction "3_3") (pintype "passive"))
      (node (ref "AUX") (pin "4") (pinfunction "4_4") (pintype "passive"))
      (node (ref "FanSel") (pin "1") (pinfunction "1_1") (pintype "passive"))
      (node (ref "J1") (pin "24") (pinfunction "24_24") (pintype "passive"))
      (node (ref "J2") (pin "23") (pinfunction "23_23") (pintype "passive"))
      (node (ref "J3") (pin "19") (pinfunction "19_19") (pintype "passive"))
      (node (ref "J3") (pin "20") (pinfunction "20_20") (pintype "passive"))
      (node (ref "J3") (pin "31") (pinfunction "31_31") (pintype "passive"))
      (node (ref "J3") (pin "32") (pinfunction "32_32") (pintype "passive"))
      (node (ref "J3") (pin "7") (pinfunction "7_7") (pintype "passive"))
      (node (ref "J3") (pin "8") (pinfunction "8_8") (pintype "passive"))
      (node (ref "J4") (pin "19") (pinfunction "19_19") (pintype "passive"))
      (node (ref "J4") (pin "20") (pinfunction "20_20") (pintype "passive"))
      (node (ref "J4") (pin "31") (pinfunction "31_31") (pintype "passive"))
      (node (ref "J4") (pin "32") (pinfunction "32_32") (pintype "passive"))
      (node (ref "J4") (pin "7") (pinfunction "7_7") (pintype "passive"))
      (node (ref "J4") (pin "8") (pinfunction "8_8") (pintype "passive"))
    )
    (net (code "128") (name "VCC33") (class "Default")
      (node (ref "J1") (pin "2") (pinfunction "2_2") (pintype "passive"))
      (node (ref "J2") (pin "1") (pinfunction "1_1") (pintype "passive"))
    )
    (net (code "129") (name "VS") (class "Default")
      (node (ref "J3") (pin "11") (pinfunction "11_11") (pintype "passive"))
      (node (ref "J3") (pin "12") (pinfunction "12_12") (pintype "passive"))
      (node (ref "J3") (pin "23") (pinfunction "23_23") (pintype "passive"))
      (node (ref "J3") (pin "24") (pinfunction "24_24") (pintype "passive"))
      (node (ref "J3") (pin "35") (pinfunction "35_35") (pintype "passive"))
      (node (ref "J3") (pin "36") (pinfunction "36_36") (pintype "passive"))
      (node (ref "J4") (pin "11") (pinfunction "11_11") (pintype "passive"))
      (node (ref "J4") (pin "12") (pinfunction "12_12") (pintype "passive"))
      (node (ref "J4") (pin "23") (pinfunction "23_23") (pintype "passive"))
      (node (ref "J4") (pin "24") (pinfunction "24_24") (pintype "passive"))
      (node (ref "J4") (pin "35") (pinfunction "35_35") (pintype "passive"))
      (node (ref "J4") (pin "36") (pinfunction "36_36") (pintype "passive"))
    )
    (net (code "130") (name "unconnected-(J1-Pad10)") (class "Default")
      (node (ref "J1") (pin "10") (pinfunction "10_10") (pintype "passive"))
    )
    (net (code "131") (name "unconnected-(J1-Pad12)") (class "Default")
      (node (ref "J1") (pin "12") (pinfunction "12_12") (pintype "passive"))
    )
    (net (code "132") (name "unconnected-(J1-Pad14)") (class "Default")
      (node (ref "J1") (pin "14") (pinfunction "14_14") (pintype "passive"))
    )
    (net (code "133") (name "unconnected-(J1-Pad16)") (class "Default")
      (node (ref "J1") (pin "16") (pinfunction "16_16") (pintype "passive"))
    )
    (net (code "134") (name "unconnected-(J1-Pad18)") (class "Default")
      (node (ref "J1") (pin "18") (pinfunction "18_18") (pintype "passive"))
    )
    (net (code "135") (name "unconnected-(J1-Pad20)") (class "Default")
      (node (ref "J1") (pin "20") (pinfunction "20_20") (pintype "passive"))
    )
    (net (code "136") (name "unconnected-(J1-Pad22)") (class "Default")
      (node (ref "J1") (pin "22") (pinfunction "22_22") (pintype "passive"))
    )
    (net (code "137") (name "unconnected-(J1-Pad26)") (class "Default")
      (node (ref "J1") (pin "26") (pinfunction "26_26") (pintype "passive"))
    )
    (net (code "138") (name "unconnected-(J1-Pad28)") (class "Default")
      (node (ref "J1") (pin "28") (pinfunction "28_28") (pintype "passive"))
    )
    (net (code "139") (name "unconnected-(J1-Pad30)") (class "Default")
      (node (ref "J1") (pin "30") (pinfunction "30_30") (pintype "passive"))
    )
    (net (code "140") (name "unconnected-(J1-Pad32)") (class "Default")
      (node (ref "J1") (pin "32") (pinfunction "32_32") (pintype "passive"))
    )
    (net (code "141") (name "unconnected-(J1-Pad34)") (class "Default")
      (node (ref "J1") (pin "34") (pinfunction "34_34") (pintype "passive"))
    )
    (net (code "142") (name "unconnected-(J1-Pad36)") (class "Default")
      (node (ref "J1") (pin "36") (pinfunction "36_36") (pintype "passive"))
    )
    (net (code "143") (name "unconnected-(J1-Pad38)") (class "Default")
      (node (ref "J1") (pin "38") (pinfunction "38_38") (pintype "passive"))
    )
    (net (code "144") (name "unconnected-(J1-Pad40)") (class "Default")
      (node (ref "J1") (pin "40") (pinfunction "40_40") (pintype "passive"))
    )
    (net (code "145") (name "unconnected-(J1-Pad52)") (class "Default")
      (node (ref "J1") (pin "52") (pinfunction "52_52") (pintype "passive"))
    )
    (net (code "146") (name "unconnected-(J2-Pad3)") (class "Default")
      (node (ref "J2") (pin "3") (pinfunction "3_3") (pintype "passive"))
    )
    (net (code "147") (name "unconnected-(J2-Pad5)") (class "Default")
      (node (ref "J2") (pin "5") (pinfunction "5_5") (pintype "passive"))
    )
    (net (code "148") (name "unconnected-(J2-Pad7)") (class "Default")
      (node (ref "J2") (pin "7") (pinfunction "7_7") (pintype "passive"))
    )
    (net (code "149") (name "unconnected-(J2-Pad9)") (class "Default")
      (node (ref "J2") (pin "9") (pinfunction "9_9") (pintype "passive"))
    )
    (net (code "150") (name "unconnected-(J2-Pad11)") (class "Default")
      (node (ref "J2") (pin "11") (pinfunction "11_11") (pintype "passive"))
    )
    (net (code "151") (name "unconnected-(J2-Pad13)") (class "Default")
      (node (ref "J2") (pin "13") (pinfunction "13_13") (pintype "passive"))
    )
    (net (code "152") (name "unconnected-(J2-Pad15)") (class "Default")
      (node (ref "J2") (pin "15") (pinfunction "15_15") (pintype "passive"))
    )
    (net (code "153") (name "unconnected-(J2-Pad17)") (class "Default")
      (node (ref "J2") (pin "17") (pinfunction "17_17") (pintype "passive"))
    )
    (net (code "154") (name "unconnected-(J2-Pad19)") (class "Default")
      (node (ref "J2") (pin "19") (pinfunction "19_19") (pintype "passive"))
    )
    (net (code "155") (name "unconnected-(J2-Pad21)") (class "Default")
      (node (ref "J2") (pin "21") (pinfunction "21_21") (pintype "passive"))
    )
    (net (code "156") (name "unconnected-(J2-Pad25)") (class "Default")
      (node (ref "J2") (pin "25") (pinfunction "25_25") (pintype "passive"))
    )
    (net (code "157") (name "unconnected-(J2-Pad27)") (class "Default")
      (node (ref "J2") (pin "27") (pinfunction "27_27") (pintype "passive"))
    )
    (net (code "158") (name "unconnected-(J2-Pad29)") (class "Default")
      (node (ref "J2") (pin "29") (pinfunction "29_29") (pintype "passive"))
    )
  )
)
